# Sheet_LED.net
KiCad netlist of a schematic drawn in Altium Designer
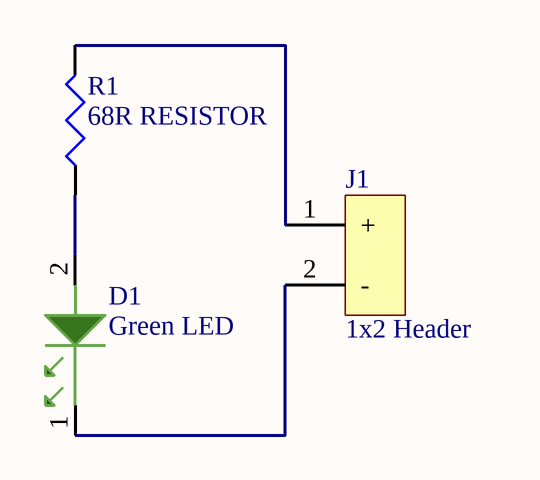
[diagram p0: Sheet_LED.SchDoc]

(export (version "E")
  (design (tool "Eeschema 10.0.6"))
  (components
    (comp (ref "D1")
      (value "Green LED")
      (footprint "GREEN_LED")
      (description "WL-SMCD SMT Mono-color Chip LED Diffused")
      (fields
        (field (name "MANUFACTURER") "Wurth Electronics")
        (field (name "MANUFACTURER PART NUMBER") "150060VS55040")
      )
      (libsource (lib "LED") (part "150060VS55040"))
    )
    (comp (ref "J1")
      (value "1x2 Header")
      (footprint "Molex_1x2")
      (description "KK 254 Wire-to-Board Header, Vertical, with Friction Lock, 2 Circuits, Gold (Au) Plating")
      (fields (field (name "MANUFACTURER") "Molex") (field (name "MANUFACTURER PART NUMBER") "22-29-2021"))
      (libsource (lib "LED") (part "22-29-2021"))
    )
    (comp (ref "R1")
      (value "68R RESISTOR")
      (footprint "R68")
      (description "SMD Chip Resistor, 68 Ohm, ± 1%, 125 mW, 0805 [2012 Metric], Thick Film, General Purpose")
      (fields
        (field (name "MANUFACTURER") "Vishay")
        (field (name "MANUFACTURER PART NUMBER") "CRCW080568R0FKEAC")
      )
      (libsource (lib "LED") (part "CRCW080568R0FKEAC"))
    )
  )
  (nets
    (net (code "1") (name "Net-(D1-Pad2)") (class "Default")
      (node (ref "D1") (pin "2") (pintype "passive"))
      (node (ref "R1") (pin "1") (pintype "passive"))
    )
    (net (code "2") (name "Net-(J1-+)") (class "Default")
      (node (ref "J1") (pin "1") (pinfunction "+_1") (pintype "passive"))
      (node (ref "R1") (pin "2") (pintype "passive"))
    )
    (net (code "3") (name "Net-(J1--)") (class "Default")
      (node (ref "D1") (pin "1") (pintype "passive"))
      (node (ref "J1") (pin "2") (pinfunction "-_2") (pintype "passive"))
    )
  )
)
